# nrf52832bob.net
KiCad netlist of a schematic drawn in EAGLE
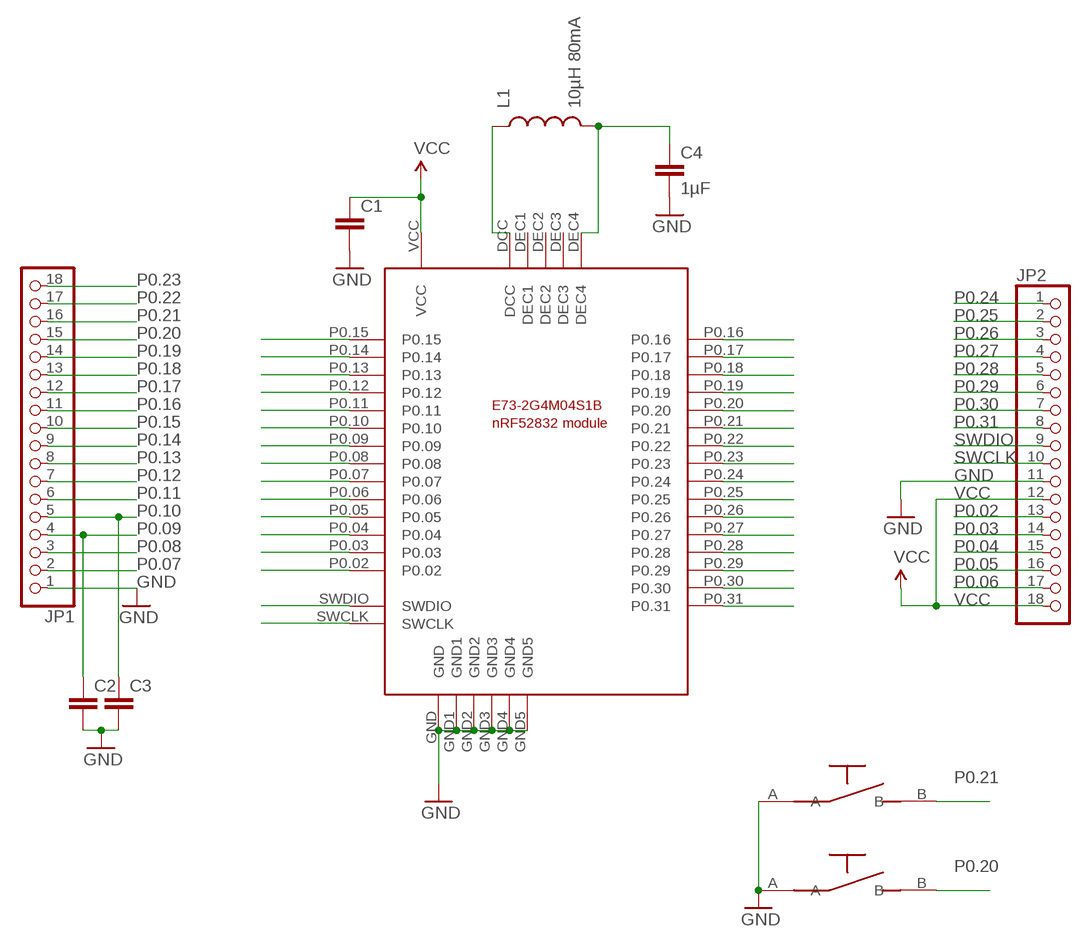
[diagram p0: schematic, sheet 1]

(export (version "E")
  (design (tool "Eeschema 10.0.6"))
  (components
    (comp (ref "C1")
      (value "C-EUC0805")
      (footprint "eagle-import:C0805")
      (libsource (lib "eagle-import") (part "C-EUC0805"))
    )
    (comp (ref "C2")
      (value "C-EUC0603")
      (footprint "eagle-import:C0603")
      (libsource (lib "eagle-import") (part "C-EUC0603"))
    )
    (comp (ref "C3")
      (value "C-EUC0603")
      (footprint "eagle-import:C0603")
      (libsource (lib "eagle-import") (part "C-EUC0603"))
    )
    (comp (ref "C4")
      (value "1µF")
      (footprint "eagle-import:C0603")
      (libsource (lib "eagle-import") (part "C-EUC0603"))
    )
    (comp (ref "JP1")
      (value "PINHD-1X18-BIG")
      (footprint "eagle-import:1X18-BIG")
      (libsource (lib "eagle-import") (part "PINHD-1X18-BIG"))
    )
    (comp (ref "JP2")
      (value "PINHD-1X18-BIG")
      (footprint "eagle-import:1X18-BIG")
      (libsource (lib "eagle-import") (part "PINHD-1X18-BIG"))
    )
    (comp (ref "L1")
      (value "10µH 80mA")
      (footprint "eagle-import:0603")
      (libsource (lib "eagle-import") (part "INDUCTOR0603"))
    )
    (comp (ref "U$1")
      (value "NRF52832MODULE")
      (footprint "eagle-import:NRF52832MODULE")
      (libsource (lib "eagle-import") (part "NRF52832MODULE"))
    )
    (comp (ref "U$2")
      (value "SWITCH2PIN")
      (footprint "eagle-import:SWITCH2PIN")
      (libsource (lib "eagle-import") (part "SWITCH2PIN"))
    )
    (comp (ref "U$3")
      (value "SWITCH2PIN")
      (footprint "eagle-import:SWITCH2PIN")
      (libsource (lib "eagle-import") (part "SWITCH2PIN"))
    )
  )
  (nets
    (net (code "1") (name "/P0.02") (class "Default")
      (node (ref "JP2") (pin "13") (pinfunction "13_13") (pintype "passive"))
      (node (ref "U$1") (pin "P0.02") (pinfunction "P0.02_P0.02") (pintype "bidirectional"))
    )
    (net (code "2") (name "/P0.03") (class "Default")
      (node (ref "JP2") (pin "14") (pinfunction "14_14") (pintype "passive"))
      (node (ref "U$1") (pin "P0.03") (pinfunction "P0.03_P0.03") (pintype "bidirectional"))
    )
    (net (code "3") (name "/P0.04") (class "Default")
      (node (ref "JP2") (pin "15") (pinfunction "15_15") (pintype "passive"))
      (node (ref "U$1") (pin "P0.04") (pinfunction "P0.04_P0.04") (pintype "bidirectional"))
    )
    (net (code "4") (name "/P0.05") (class "Default")
      (node (ref "JP2") (pin "16") (pinfunction "16_16") (pintype "passive"))
      (node (ref "U$1") (pin "P0.05") (pinfunction "P0.05_P0.05") (pintype "bidirectional"))
    )
    (net (code "5") (name "/P0.06") (class "Default")
      (node (ref "JP2") (pin "17") (pinfunction "17_17") (pintype "passive"))
      (node (ref "U$1") (pin "P0.06") (pinfunction "P0.06_P0.06") (pintype "bidirectional"))
    )
    (net (code "6") (name "/P0.07") (class "Default")
      (node (ref "JP1") (pin "2") (pinfunction "2_2") (pintype "passive"))
      (node (ref "U$1") (pin "P0.07") (pinfunction "P0.07_P0.07") (pintype "bidirectional"))
    )
    (net (code "7") (name "/P0.08") (class "Default")
      (node (ref "JP1") (pin "3") (pinfunction "3_3") (pintype "passive"))
      (node (ref "U$1") (pin "P0.08") (pinfunction "P0.08_P0.08") (pintype "bidirectional"))
    )
    (net (code "8") (name "/P0.09") (class "Default")
      (node (ref "C2") (pin "1") (pinfunction "1_1") (pintype "passive"))
      (node (ref "JP1") (pin "4") (pinfunction "4_4") (pintype "passive"))
      (node (ref "U$1") (pin "P0.09") (pinfunction "P0.09_P0.09") (pintype "bidirectional"))
    )
    (net (code "9") (name "/P0.10") (class "Default")
      (node (ref "C3") (pin "1") (pinfunction "1_1") (pintype "passive"))
      (node (ref "JP1") (pin "5") (pinfunction "5_5") (pintype "passive"))
      (node (ref "U$1") (pin "P0.10") (pinfunction "P0.10_P0.10") (pintype "bidirectional"))
    )
    (net (code "10") (name "/P0.11") (class "Default")
      (node (ref "JP1") (pin "6") (pinfunction "6_6") (pintype "passive"))
      (node (ref "U$1") (pin "P0.11") (pinfunction "P0.11_P0.11") (pintype "bidirectional"))
    )
    (net (code "11") (name "/P0.12") (class "Default")
      (node (ref "JP1") (pin "7") (pinfunction "7_7") (pintype "passive"))
      (node (ref "U$1") (pin "P0.12") (pinfunction "P0.12_P0.12") (pintype "bidirectional"))
    )
    (net (code "12") (name "/P0.13") (class "Default")
      (node (ref "JP1") (pin "8") (pinfunction "8_8") (pintype "passive"))
      (node (ref "U$1") (pin "P0.13") (pinfunction "P0.13_P0.13") (pintype "bidirectional"))
    )
    (net (code "13") (name "/P0.14") (class "Default")
      (node (ref "JP1") (pin "9") (pinfunction "9_9") (pintype "passive"))
      (node (ref "U$1") (pin "P0.14") (pinfunction "P0.14_P0.14") (pintype "bidirectional"))
    )
    (net (code "14") (name "/P0.15") (class "Default")
      (node (ref "JP1") (pin "10") (pinfunction "10_10") (pintype "passive"))
      (node (ref "U$1") (pin "P0.15") (pinfunction "P0.15_P0.15") (pintype "bidirectional"))
    )
    (net (code "15") (name "/P0.16") (class "Default")
      (node (ref "JP1") (pin "11") (pinfunction "11_11") (pintype "passive"))
      (node (ref "U$1") (pin "P0.16") (pinfunction "P0.16_P0.16") (pintype "bidirectional"))
    )
    (net (code "16") (name "/P0.17") (class "Default")
      (node (ref "JP1") (pin "12") (pinfunction "12_12") (pintype "passive"))
      (node (ref "U$1") (pin "P0.17") (pinfunction "P0.17_P0.17") (pintype "bidirectional"))
    )
    (net (code "17") (name "/P0.18") (class "Default")
      (node (ref "JP1") (pin "13") (pinfunction "13_13") (pintype "passive"))
      (node (ref "U$1") (pin "P0.18") (pinfunction "P0.18_P0.18") (pintype "bidirectional"))
    )
    (net (code "18") (name "/P0.19") (class "Default")
      (node (ref "JP1") (pin "14") (pinfunction "14_14") (pintype "passive"))
      (node (ref "U$1") (pin "P0.19") (pinfunction "P0.19_P0.19") (pintype "bidirectional"))
    )
    (net (code "19") (name "/P0.20") (class "Default")
      (node (ref "JP1") (pin "15") (pinfunction "15_15") (pintype "passive"))
      (node (ref "U$1") (pin "P0.20") (pinfunction "P0.20_P0.20") (pintype "bidirectional"))
      (node (ref "U$3") (pin "B") (pinfunction "B_B") (pintype "bidirectional"))
    )
    (net (code "20") (name "/P0.21") (class "Default")
      (node (ref "JP1") (pin "16") (pinfunction "16_16") (pintype "passive"))
      (node (ref "U$1") (pin "P0.21") (pinfunction "P0.21_P0.21") (pintype "bidirectional"))
      (node (ref "U$2") (pin "B") (pinfunction "B_B") (pintype "bidirectional"))
    )
    (net (code "21") (name "/P0.22") (class "Default")
      (node (ref "JP1") (pin "17") (pinfunction "17_17") (pintype "passive"))
      (node (ref "U$1") (pin "P0.22") (pinfunction "P0.22_P0.22") (pintype "bidirectional"))
    )
    (net (code "22") (name "/P0.23") (class "Default")
      (node (ref "JP1") (pin "18") (pinfunction "18_18") (pintype "passive"))
      (node (ref "U$1") (pin "P0.23") (pinfunction "P0.23_P0.23") (pintype "bidirectional"))
    )
    (net (code "23") (name "/P0.24") (class "Default")
      (node (ref "JP2") (pin "1") (pinfunction "1_1") (pintype "passive"))
      (node (ref "U$1") (pin "P0.24") (pinfunction "P0.24_P0.24") (pintype "bidirectional"))
    )
    (net (code "24") (name "/P0.25") (class "Default")
      (node (ref "JP2") (pin "2") (pinfunction "2_2") (pintype "passive"))
      (node (ref "U$1") (pin "P0.25") (pinfunction "P0.25_P0.25") (pintype "bidirectional"))
    )
    (net (code "25") (name "/P0.26") (class "Default")
      (node (ref "JP2") (pin "3") (pinfunction "3_3") (pintype "passive"))
      (node (ref "U$1") (pin "P0.26") (pinfunction "P0.26_P0.26") (pintype "bidirectional"))
    )
    (net (code "26") (name "/P0.27") (class "Default")
      (node (ref "JP2") (pin "4") (pinfunction "4_4") (pintype "passive"))
      (node (ref "U$1") (pin "P0.27") (pinfunction "P0.27_P0.27") (pintype "bidirectional"))
    )
    (net (code "27") (name "/P0.28") (class "Default")
      (node (ref "JP2") (pin "5") (pinfunction "5_5") (pintype "passive"))
      (node (ref "U$1") (pin "P0.28") (pinfunction "P0.28_P0.28") (pintype "bidirectional"))
    )
    (net (code "28") (name "/P0.29") (class "Default")
      (node (ref "JP2") (pin "6") (pinfunction "6_6") (pintype "passive"))
      (node (ref "U$1") (pin "P0.29") (pinfunction "P0.29_P0.29") (pintype "bidirectional"))
    )
    (net (code "29") (name "/P0.30") (class "Default")
      (node (ref "JP2") (pin "7") (pinfunction "7_7") (pintype "passive"))
      (node (ref "U$1") (pin "P0.30") (pinfunction "P0.30_P0.30") (pintype "bidirectional"))
    )
    (net (code "30") (name "/P0.31") (class "Default")
      (node (ref "JP2") (pin "8") (pinfunction "8_8") (pintype "passive"))
      (node (ref "U$1") (pin "P0.31") (pinfunction "P0.31_P0.31") (pintype "bidirectional"))
    )
    (net (code "31") (name "/SWCLK") (class "Default")
      (node (ref "JP2") (pin "10") (pinfunction "10_10") (pintype "passive"))
      (node (ref "U$1") (pin "SWCLK") (pinfunction "SWCLK_SWCLK") (pintype "bidirectional"))
    )
    (net (code "32") (name "/SWDIO") (class "Default")
      (node (ref "JP2") (pin "9") (pinfunction "9_9") (pintype "passive"))
      (node (ref "U$1") (pin "SWDIO") (pinfunction "SWDIO_SWDIO") (pintype "bidirectional"))
    )
    (net (code "33") (name "GND") (class "Default")
      (node (ref "C1") (pin "2") (pinfunction "2_2") (pintype "passive"))
      (node (ref "C2") (pin "2") (pinfunction "2_2") (pintype "passive"))
      (node (ref "C3") (pin "2") (pinfunction "2_2") (pintype "passive"))
      (node (ref "C4") (pin "2") (pinfunction "2_2") (pintype "passive"))
      (node (ref "JP1") (pin "1") (pinfunction "1_1") (pintype "passive"))
      (node (ref "JP2") (pin "11") (pinfunction "11_11") (pintype "passive"))
      (node (ref "U$1") (pin "GND") (pinfunction "GND_GND") (pintype "bidirectional"))
      (node (ref "U$1") (pin "GND1") (pinfunction "GND1_GND1") (pintype "bidirectional"))
      (node (ref "U$1") (pin "GND2") (pinfunction "GND2_GND2") (pintype "bidirectional"))
      (node (ref "U$1") (pin "GND3") (pinfunction "GND3_GND3") (pintype "bidirectional"))
      (node (ref "U$1") (pin "GND4") (pinfunction "GND4_GND4") (pintype "bidirectional"))
      (node (ref "U$1") (pin "GND5") (pinfunction "GND5_GND5") (pintype "bidirectional"))
      (node (ref "U$2") (pin "A") (pinfunction "A_A") (pintype "bidirectional"))
      (node (ref "U$3") (pin "A") (pinfunction "A_A") (pintype "bidirectional"))
    )
    (net (code "34") (name "Net-(C4-Pad1)") (class "Default")
      (node (ref "C4") (pin "1") (pinfunction "1_1") (pintype "passive"))
      (node (ref "L1") (pin "2") (pinfunction "2_2") (pintype "passive"))
      (node (ref "U$1") (pin "DEC4") (pinfunction "DEC4_DEC4") (pintype "bidirectional"))
    )
    (net (code "35") (name "Net-(L1-Pad1)") (class "Default")
      (node (ref "L1") (pin "1") (pinfunction "1_1") (pintype "passive"))
      (node (ref "U$1") (pin "DCC") (pinfunction "DCC_DCC") (pintype "bidirectional"))
    )
    (net (code "36") (name "VCC") (class "Default")
      (node (ref "C1") (pin "1") (pinfunction "1_1") (pintype "passive"))
      (node (ref "JP2") (pin "12") (pinfunction "12_12") (pintype "passive"))
      (node (ref "JP2") (pin "18") (pinfunction "18_18") (pintype "passive"))
      (node (ref "U$1") (pin "VCC") (pinfunction "VCC_VCC") (pintype "bidirectional"))
    )
    (net (code "37") (name "unconnected-(U$1-PadDEC1)") (class "Default")
      (node (ref "U$1") (pin "DEC1") (pinfunction "DEC1_DEC1") (pintype "bidirectional"))
    )
    (net (code "38") (name "unconnected-(U$1-PadDEC2)") (class "Default")
      (node (ref "U$1") (pin "DEC2") (pinfunction "DEC2_DEC2") (pintype "bidirectional"))
    )
    (net (code "39") (name "unconnected-(U$1-PadDEC3)") (class "Default")
      (node (ref "U$1") (pin "DEC3") (pinfunction "DEC3_DEC3") (pintype "bidirectional"))
    )
  )
)
